# HandlesRegenerated.net
KiCad netlist of a schematic drawn in EAGLE
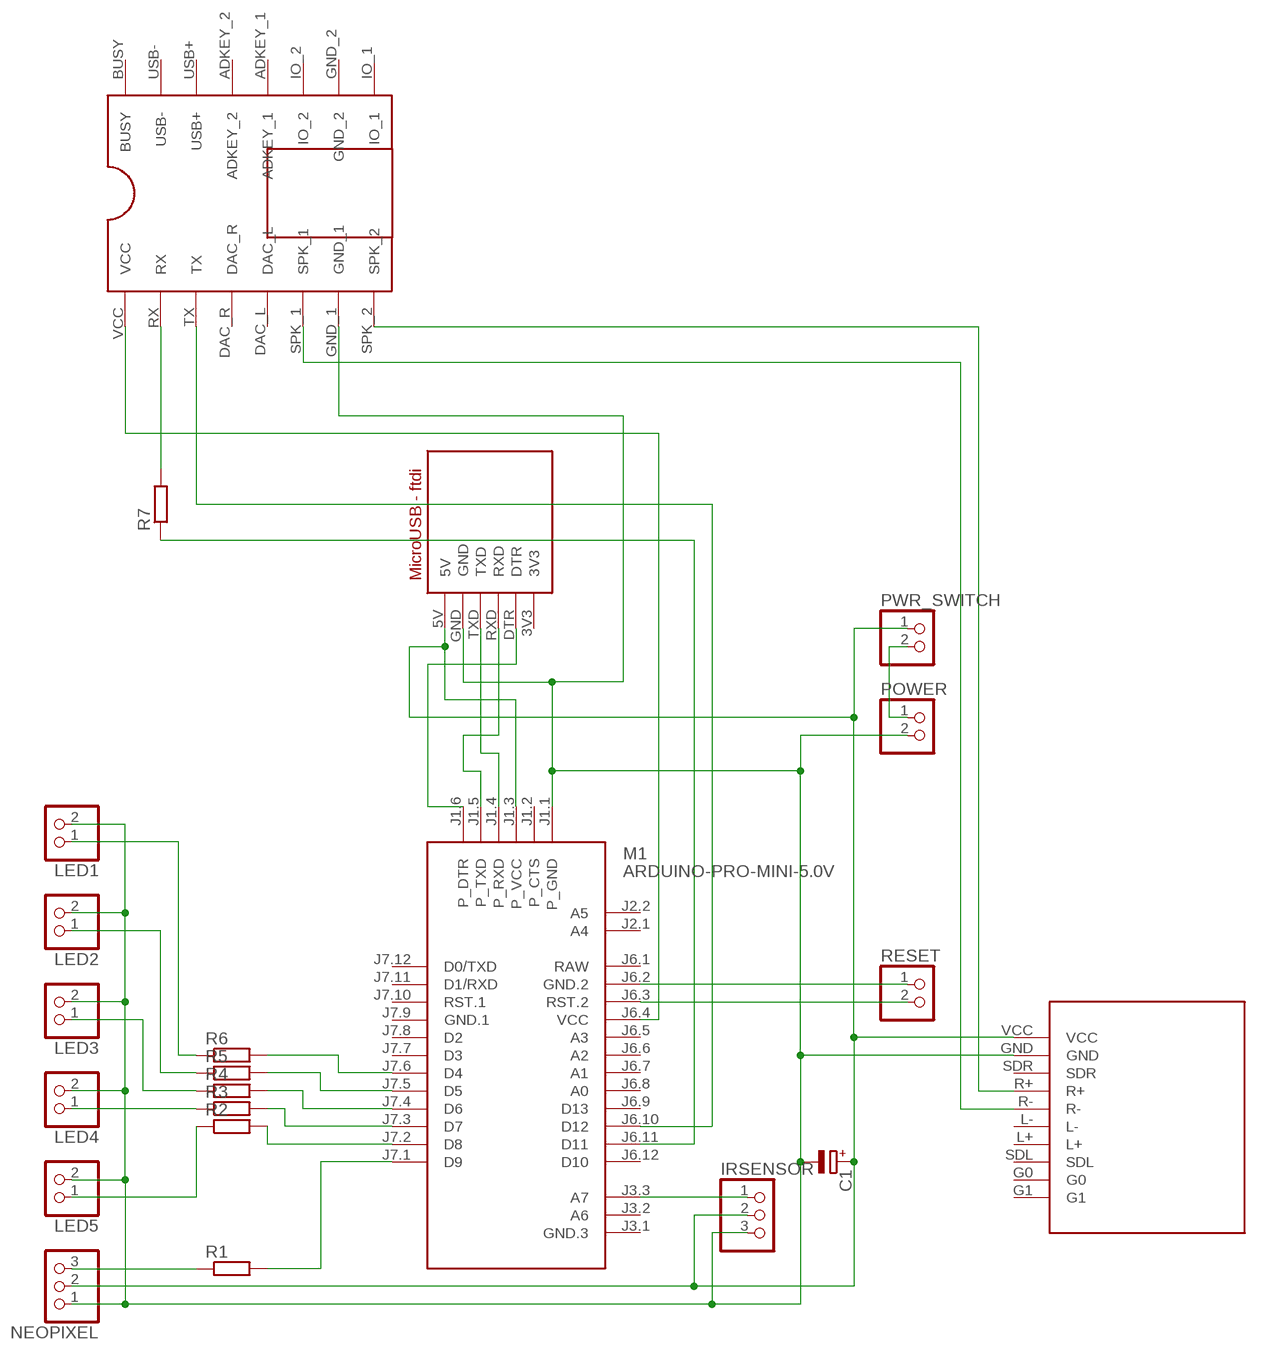
[diagram p0: schematic, sheet 1]

(export (version "E")
  (design (tool "Eeschema 10.0.6"))
  (components
    (comp (ref "C1")
      (value "CPOL-EUE2,5-6E")
      (footprint "eagle-import:E2,5-6E")
      (libsource (lib "eagle-import") (part "CPOL-EUE2,5-6E"))
    )
    (comp (ref "IRSENSOR")
      (value "PINHD-1X3")
      (footprint "eagle-import:1X03")
      (libsource (lib "eagle-import") (part "PINHD-1X3"))
    )
    (comp (ref "LED1")
      (value "PINHD-1X2")
      (footprint "eagle-import:1X02")
      (libsource (lib "eagle-import") (part "PINHD-1X2"))
    )
    (comp (ref "LED2")
      (value "PINHD-1X2")
      (footprint "eagle-import:1X02")
      (libsource (lib "eagle-import") (part "PINHD-1X2"))
    )
    (comp (ref "LED3")
      (value "PINHD-1X2")
      (footprint "eagle-import:1X02")
      (libsource (lib "eagle-import") (part "PINHD-1X2"))
    )
    (comp (ref "LED4")
      (value "PINHD-1X2")
      (footprint "eagle-import:1X02")
      (libsource (lib "eagle-import") (part "PINHD-1X2"))
    )
    (comp (ref "LED5")
      (value "PINHD-1X2")
      (footprint "eagle-import:1X02")
      (libsource (lib "eagle-import") (part "PINHD-1X2"))
    )
    (comp (ref "M1")
      (value "ARDUINO-PRO-MINI-5.0V")
      (footprint "eagle-import:ARDUINO-PRO-MINI")
      (libsource (lib "eagle-import") (part "ARDUINO-PRO-MINI-5.0V"))
    )
    (comp (ref "NEOPIXEL")
      (value "PINHD-1X3")
      (footprint "eagle-import:1X03")
      (libsource (lib "eagle-import") (part "PINHD-1X3"))
    )
    (comp (ref "POWER")
      (value "PINHD-1X2")
      (footprint "eagle-import:1X02")
      (libsource (lib "eagle-import") (part "PINHD-1X2"))
    )
    (comp (ref "PWR_SWITCH")
      (value "PINHD-1X2")
      (footprint "eagle-import:1X02")
      (libsource (lib "eagle-import") (part "PINHD-1X2"))
    )
    (comp (ref "R1")
      (value "R-EU_0204/7")
      (footprint "eagle-import:0204_7")
      (libsource (lib "eagle-import") (part "R-EU_0204/7"))
    )
    (comp (ref "R2")
      (value "R-EU_0204/7")
      (footprint "eagle-import:0204_7")
      (libsource (lib "eagle-import") (part "R-EU_0204/7"))
    )
    (comp (ref "R3")
      (value "R-EU_0204/7")
      (footprint "eagle-import:0204_7")
      (libsource (lib "eagle-import") (part "R-EU_0204/7"))
    )
    (comp (ref "R4")
      (value "R-EU_0204/7")
      (footprint "eagle-import:0204_7")
      (libsource (lib "eagle-import") (part "R-EU_0204/7"))
    )
    (comp (ref "R5")
      (value "R-EU_0204/7")
      (footprint "eagle-import:0204_7")
      (libsource (lib "eagle-import") (part "R-EU_0204/7"))
    )
    (comp (ref "R6")
      (value "R-EU_0204/7")
      (footprint "eagle-import:0204_7")
      (libsource (lib "eagle-import") (part "R-EU_0204/7"))
    )
    (comp (ref "R7")
      (value "R-EU_0207/7")
      (footprint "eagle-import:0207_7")
      (libsource (lib "eagle-import") (part "resistor_R-EU_0207/7"))
    )
    (comp (ref "RESET")
      (value "PINHD-1X2")
      (footprint "eagle-import:1X02")
      (libsource (lib "eagle-import") (part "PINHD-1X2"))
    )
    (comp (ref "U$1")
      (value "MICRO-USB-DEV")
      (footprint "eagle-import:MICRO-USB-PAC")
      (libsource (lib "eagle-import") (part "MICRO-USB-DEV"))
    )
    (comp (ref "U$2")
      (value "STEREO-AUDIO-AMP-DEV")
      (footprint "eagle-import:STEREO-AUDIO-AMP-PAC")
      (libsource (lib "eagle-import") (part "STEREO-AUDIO-AMP-DEV"))
    )
    (comp (ref "U$3")
      (value "DPLAYER-MINI-DEV")
      (footprint "eagle-import:DPLAYER-MINI-PAC")
      (libsource (lib "eagle-import") (part "DPLAYER-MINI-DEV"))
    )
  )
  (nets
    (net (code "1") (name "/3V3") (class "Default")
      (node (ref "U$1") (pin "3V3") (pinfunction "3V3_3V3") (pintype "power_in"))
    )
    (net (code "2") (name "/G0") (class "Default")
      (node (ref "U$2") (pin "G0") (pinfunction "G0_G0") (pintype "power_in"))
    )
    (net (code "3") (name "/G1") (class "Default")
      (node (ref "U$2") (pin "G1") (pinfunction "G1_G1") (pintype "power_in"))
    )
    (net (code "4") (name "/GND.1") (class "Default")
      (node (ref "M1") (pin "J7.9") (pinfunction "GND.1_J7.9") (pintype "power_in"))
    )
    (net (code "5") (name "/GND_2") (class "Default")
      (node (ref "U$3") (pin "GND_2") (pinfunction "GND_2_GND_2") (pintype "power_in"))
    )
    (net (code "6") (name "/RAW") (class "Default")
      (node (ref "M1") (pin "J6.1") (pinfunction "RAW_J6.1") (pintype "power_in"))
    )
    (net (code "7") (name "Net-(LED1-Pad1)") (class "Default")
      (node (ref "LED1") (pin "1") (pinfunction "1_1") (pintype "passive"))
      (node (ref "R6") (pin "1") (pinfunction "1_1") (pintype "passive"))
    )
    (net (code "8") (name "Net-(LED2-Pad1)") (class "Default")
      (node (ref "LED2") (pin "1") (pinfunction "1_1") (pintype "passive"))
      (node (ref "R5") (pin "1") (pinfunction "1_1") (pintype "passive"))
    )
    (net (code "9") (name "Net-(LED3-Pad1)") (class "Default")
      (node (ref "LED3") (pin "1") (pinfunction "1_1") (pintype "passive"))
      (node (ref "R4") (pin "1") (pinfunction "1_1") (pintype "passive"))
    )
    (net (code "10") (name "Net-(LED4-Pad1)") (class "Default")
      (node (ref "LED4") (pin "1") (pinfunction "1_1") (pintype "passive"))
      (node (ref "R3") (pin "1") (pinfunction "1_1") (pintype "passive"))
    )
    (net (code "11") (name "Net-(LED5-Pad1)") (class "Default")
      (node (ref "LED5") (pin "1") (pinfunction "1_1") (pintype "passive"))
      (node (ref "R2") (pin "1") (pinfunction "1_1") (pintype "passive"))
    )
    (net (code "12") (name "Net-(M1-A7)") (class "Default")
      (node (ref "IRSENSOR") (pin "1") (pinfunction "1_1") (pintype "passive"))
      (node (ref "M1") (pin "J3.3") (pinfunction "A7_J3.3") (pintype "bidirectional"))
    )
    (net (code "13") (name "Net-(M1-D4)") (class "Default")
      (node (ref "M1") (pin "J7.6") (pinfunction "D4_J7.6") (pintype "bidirectional"))
      (node (ref "R6") (pin "2") (pinfunction "2_2") (pintype "passive"))
    )
    (net (code "14") (name "Net-(M1-D5)") (class "Default")
      (node (ref "M1") (pin "J7.5") (pinfunction "D5_J7.5") (pintype "bidirectional"))
      (node (ref "R5") (pin "2") (pinfunction "2_2") (pintype "passive"))
    )
    (net (code "15") (name "Net-(M1-D6)") (class "Default")
      (node (ref "M1") (pin "J7.4") (pinfunction "D6_J7.4") (pintype "bidirectional"))
      (node (ref "R4") (pin "2") (pinfunction "2_2") (pintype "passive"))
    )
    (net (code "16") (name "Net-(M1-D7)") (class "Default")
      (node (ref "M1") (pin "J7.3") (pinfunction "D7_J7.3") (pintype "bidirectional"))
      (node (ref "R3") (pin "2") (pinfunction "2_2") (pintype "passive"))
    )
    (net (code "17") (name "Net-(M1-D8)") (class "Default")
      (node (ref "M1") (pin "J7.2") (pinfunction "D8_J7.2") (pintype "bidirectional"))
      (node (ref "R2") (pin "2") (pinfunction "2_2") (pintype "passive"))
    )
    (net (code "18") (name "Net-(M1-D9)") (class "Default")
      (node (ref "M1") (pin "J7.1") (pinfunction "D9_J7.1") (pintype "bidirectional"))
      (node (ref "R1") (pin "2") (pinfunction "2_2") (pintype "passive"))
    )
    (net (code "19") (name "Net-(M1-D11)") (class "Default")
      (node (ref "M1") (pin "J6.11") (pinfunction "D11_J6.11") (pintype "bidirectional"))
      (node (ref "R7") (pin "1") (pinfunction "1_1") (pintype "passive"))
    )
    (net (code "20") (name "Net-(M1-D12)") (class "Default")
      (node (ref "M1") (pin "J6.10") (pinfunction "D12_J6.10") (pintype "bidirectional"))
      (node (ref "U$3") (pin "TX") (pinfunction "TX_TX") (pintype "bidirectional"))
    )
    (net (code "21") (name "Net-(M1-GND.2)") (class "Default")
      (node (ref "M1") (pin "J6.2") (pinfunction "GND.2_J6.2") (pintype "power_in"))
      (node (ref "RESET") (pin "1") (pinfunction "1_1") (pintype "passive"))
    )
    (net (code "22") (name "Net-(M1-P_DTR)") (class "Default")
      (node (ref "M1") (pin "J1.6") (pinfunction "P_DTR_J1.6") (pintype "bidirectional"))
      (node (ref "U$1") (pin "DTR") (pinfunction "DTR_DTR") (pintype "power_in"))
    )
    (net (code "23") (name "Net-(M1-P_GND)") (class "Default")
      (node (ref "C1") (pin "-") (pinfunction "-_-") (pintype "passive"))
      (node (ref "IRSENSOR") (pin "3") (pinfunction "3_3") (pintype "passive"))
      (node (ref "LED1") (pin "2") (pinfunction "2_2") (pintype "passive"))
      (node (ref "LED2") (pin "2") (pinfunction "2_2") (pintype "passive"))
      (node (ref "LED3") (pin "2") (pinfunction "2_2") (pintype "passive"))
      (node (ref "LED4") (pin "2") (pinfunction "2_2") (pintype "passive"))
      (node (ref "LED5") (pin "2") (pinfunction "2_2") (pintype "passive"))
      (node (ref "M1") (pin "J1.1") (pinfunction "P_GND_J1.1") (pintype "bidirectional"))
      (node (ref "NEOPIXEL") (pin "1") (pinfunction "1_1") (pintype "passive"))
      (node (ref "POWER") (pin "2") (pinfunction "2_2") (pintype "passive"))
      (node (ref "U$1") (pin "GND") (pinfunction "GND_GND") (pintype "bidirectional"))
      (node (ref "U$2") (pin "GND") (pinfunction "GND_GND") (pintype "power_in"))
      (node (ref "U$3") (pin "GND_1") (pinfunction "GND_1_GND_1") (pintype "power_in"))
    )
    (net (code "24") (name "Net-(M1-P_RXD)") (class "Default")
      (node (ref "M1") (pin "J1.4") (pinfunction "P_RXD_J1.4") (pintype "bidirectional"))
      (node (ref "U$1") (pin "TXD") (pinfunction "TXD_TXD") (pintype "bidirectional"))
    )
    (net (code "25") (name "Net-(M1-P_TXD)") (class "Default")
      (node (ref "M1") (pin "J1.5") (pinfunction "P_TXD_J1.5") (pintype "bidirectional"))
      (node (ref "U$1") (pin "RXD") (pinfunction "RXD_RXD") (pintype "bidirectional"))
    )
    (net (code "26") (name "Net-(M1-P_VCC)") (class "Default")
      (node (ref "C1") (pin "+") (pinfunction "+_+") (pintype "passive"))
      (node (ref "IRSENSOR") (pin "2") (pinfunction "2_2") (pintype "passive"))
      (node (ref "M1") (pin "J1.3") (pinfunction "P_VCC_J1.3") (pintype "bidirectional"))
      (node (ref "NEOPIXEL") (pin "2") (pinfunction "2_2") (pintype "passive"))
      (node (ref "PWR_SWITCH") (pin "1") (pinfunction "1_1") (pintype "passive"))
      (node (ref "U$1") (pin "5V") (pinfunction "5V_5V") (pintype "power_in"))
      (node (ref "U$2") (pin "VCC") (pinfunction "VCC_VCC") (pintype "power_in"))
    )
    (net (code "27") (name "Net-(M1-RST.2)") (class "Default")
      (node (ref "M1") (pin "J6.3") (pinfunction "RST.2_J6.3") (pintype "bidirectional"))
      (node (ref "RESET") (pin "2") (pinfunction "2_2") (pintype "passive"))
    )
    (net (code "28") (name "Net-(M1-VCC)") (class "Default")
      (node (ref "M1") (pin "J6.4") (pinfunction "VCC_J6.4") (pintype "power_in"))
      (node (ref "U$3") (pin "VCC") (pinfunction "VCC_VCC") (pintype "power_in"))
    )
    (net (code "29") (name "Net-(NEOPIXEL-Pad3)") (class "Default")
      (node (ref "NEOPIXEL") (pin "3") (pinfunction "3_3") (pintype "passive"))
      (node (ref "R1") (pin "1") (pinfunction "1_1") (pintype "passive"))
    )
    (net (code "30") (name "Net-(POWER-Pad1)") (class "Default")
      (node (ref "POWER") (pin "1") (pinfunction "1_1") (pintype "passive"))
      (node (ref "PWR_SWITCH") (pin "2") (pinfunction "2_2") (pintype "passive"))
    )
    (net (code "31") (name "Net-(R7-Pad2)") (class "Default")
      (node (ref "R7") (pin "2") (pinfunction "2_2") (pintype "passive"))
      (node (ref "U$3") (pin "RX") (pinfunction "RX_RX") (pintype "bidirectional"))
    )
    (net (code "32") (name "Net-(U$2-PadR+)") (class "Default")
      (node (ref "U$2") (pin "R+") (pinfunction "R+_R+") (pintype "input"))
      (node (ref "U$3") (pin "SPK_2") (pinfunction "SPK_2_SPK_2") (pintype "bidirectional"))
    )
    (net (code "33") (name "Net-(U$2-PadR-)") (class "Default")
      (node (ref "U$2") (pin "R-") (pinfunction "R-_R-") (pintype "input"))
      (node (ref "U$3") (pin "SPK_1") (pinfunction "SPK_1_SPK_1") (pintype "bidirectional"))
    )
    (net (code "34") (name "unconnected-(M1-A0-PadJ6.8)") (class "Default")
      (node (ref "M1") (pin "J6.8") (pinfunction "A0_J6.8") (pintype "bidirectional"))
    )
    (net (code "35") (name "unconnected-(M1-A1-PadJ6.7)") (class "Default")
      (node (ref "M1") (pin "J6.7") (pinfunction "A1_J6.7") (pintype "bidirectional"))
    )
    (net (code "36") (name "unconnected-(M1-A2-PadJ6.6)") (class "Default")
      (node (ref "M1") (pin "J6.6") (pinfunction "A2_J6.6") (pintype "bidirectional"))
    )
    (net (code "37") (name "unconnected-(M1-A3-PadJ6.5)") (class "Default")
      (node (ref "M1") (pin "J6.5") (pinfunction "A3_J6.5") (pintype "bidirectional"))
    )
    (net (code "38") (name "unconnected-(M1-A4-PadJ2.1)") (class "Default")
      (node (ref "M1") (pin "J2.1") (pinfunction "A4_J2.1") (pintype "bidirectional"))
    )
    (net (code "39") (name "unconnected-(M1-A5-PadJ2.2)") (class "Default")
      (node (ref "M1") (pin "J2.2") (pinfunction "A5_J2.2") (pintype "bidirectional"))
    )
    (net (code "40") (name "unconnected-(M1-A6-PadJ3.2)") (class "Default")
      (node (ref "M1") (pin "J3.2") (pinfunction "A6_J3.2") (pintype "bidirectional"))
    )
    (net (code "41") (name "unconnected-(M1-D0{slash}TXD-PadJ7.12)") (class "Default")
      (node (ref "M1") (pin "J7.12") (pinfunction "D0/TXD_J7.12") (pintype "bidirectional"))
    )
    (net (code "42") (name "unconnected-(M1-D1{slash}RXD-PadJ7.11)") (class "Default")
      (node (ref "M1") (pin "J7.11") (pinfunction "D1/RXD_J7.11") (pintype "bidirectional"))
    )
    (net (code "43") (name "unconnected-(M1-D2-PadJ7.8)") (class "Default")
      (node (ref "M1") (pin "J7.8") (pinfunction "D2_J7.8") (pintype "bidirectional"))
    )
    (net (code "44") (name "unconnected-(M1-D3-PadJ7.7)") (class "Default")
      (node (ref "M1") (pin "J7.7") (pinfunction "D3_J7.7") (pintype "bidirectional"))
    )
    (net (code "45") (name "unconnected-(M1-D10-PadJ6.12)") (class "Default")
      (node (ref "M1") (pin "J6.12") (pinfunction "D10_J6.12") (pintype "bidirectional"))
    )
    (net (code "46") (name "unconnected-(M1-D13-PadJ6.9)") (class "Default")
      (node (ref "M1") (pin "J6.9") (pinfunction "D13_J6.9") (pintype "bidirectional"))
    )
    (net (code "47") (name "unconnected-(M1-GND.3-PadJ3.1)") (class "Default")
      (node (ref "M1") (pin "J3.1") (pinfunction "GND.3_J3.1") (pintype "bidirectional"))
    )
    (net (code "48") (name "unconnected-(M1-P_CTS-PadJ1.2)") (class "Default")
      (node (ref "M1") (pin "J1.2") (pinfunction "P_CTS_J1.2") (pintype "bidirectional"))
    )
    (net (code "49") (name "unconnected-(M1-RST.1-PadJ7.10)") (class "Default")
      (node (ref "M1") (pin "J7.10") (pinfunction "RST.1_J7.10") (pintype "bidirectional"))
    )
    (net (code "50") (name "unconnected-(U$2-PadL+)") (class "Default")
      (node (ref "U$2") (pin "L+") (pinfunction "L+_L+") (pintype "input"))
    )
    (net (code "51") (name "unconnected-(U$2-PadL-)") (class "Default")
      (node (ref "U$2") (pin "L-") (pinfunction "L-_L-") (pintype "input"))
    )
    (net (code "52") (name "unconnected-(U$2-PadSDL)") (class "Default")
      (node (ref "U$2") (pin "SDL") (pinfunction "SDL_SDL") (pintype "input"))
    )
    (net (code "53") (name "unconnected-(U$2-PadSDR)") (class "Default")
      (node (ref "U$2") (pin "SDR") (pinfunction "SDR_SDR") (pintype "input"))
    )
    (net (code "54") (name "unconnected-(U$3-PadADKEY_1)") (class "Default")
      (node (ref "U$3") (pin "ADKEY_1") (pinfunction "ADKEY_1_ADKEY_1") (pintype "bidirectional"))
    )
    (net (code "55") (name "unconnected-(U$3-PadADKEY_2)") (class "Default")
      (node (ref "U$3") (pin "ADKEY_2") (pinfunction "ADKEY_2_ADKEY_2") (pintype "bidirectional"))
    )
    (net (code "56") (name "unconnected-(U$3-PadBUSY)") (class "Default")
      (node (ref "U$3") (pin "BUSY") (pinfunction "BUSY_BUSY") (pintype "bidirectional"))
    )
    (net (code "57") (name "unconnected-(U$3-PadDAC_L)") (class "Default")
      (node (ref "U$3") (pin "DAC_L") (pinfunction "DAC_L_DAC_L") (pintype "bidirectional"))
    )
    (net (code "58") (name "unconnected-(U$3-PadDAC_R)") (class "Default")
      (node (ref "U$3") (pin "DAC_R") (pinfunction "DAC_R_DAC_R") (pintype "bidirectional"))
    )
    (net (code "59") (name "unconnected-(U$3-PadIO_1)") (class "Default")
      (node (ref "U$3") (pin "IO_1") (pinfunction "IO_1_IO_1") (pintype "bidirectional"))
    )
    (net (code "60") (name "unconnected-(U$3-PadIO_2)") (class "Default")
      (node (ref "U$3") (pin "IO_2") (pinfunction "IO_2_IO_2") (pintype "bidirectional"))
    )
    (net (code "61") (name "unconnected-(U$3-PadUSB+)") (class "Default")
      (node (ref "U$3") (pin "USB+") (pinfunction "USB+_USB+") (pintype "bidirectional"))
    )
    (net (code "62") (name "unconnected-(U$3-PadUSB-)") (class "Default")
      (node (ref "U$3") (pin "USB-") (pinfunction "USB-_USB-") (pintype "bidirectional"))
    )
  )
)
